# IoT_Shield.net
KiCad netlist of a schematic drawn in EAGLE
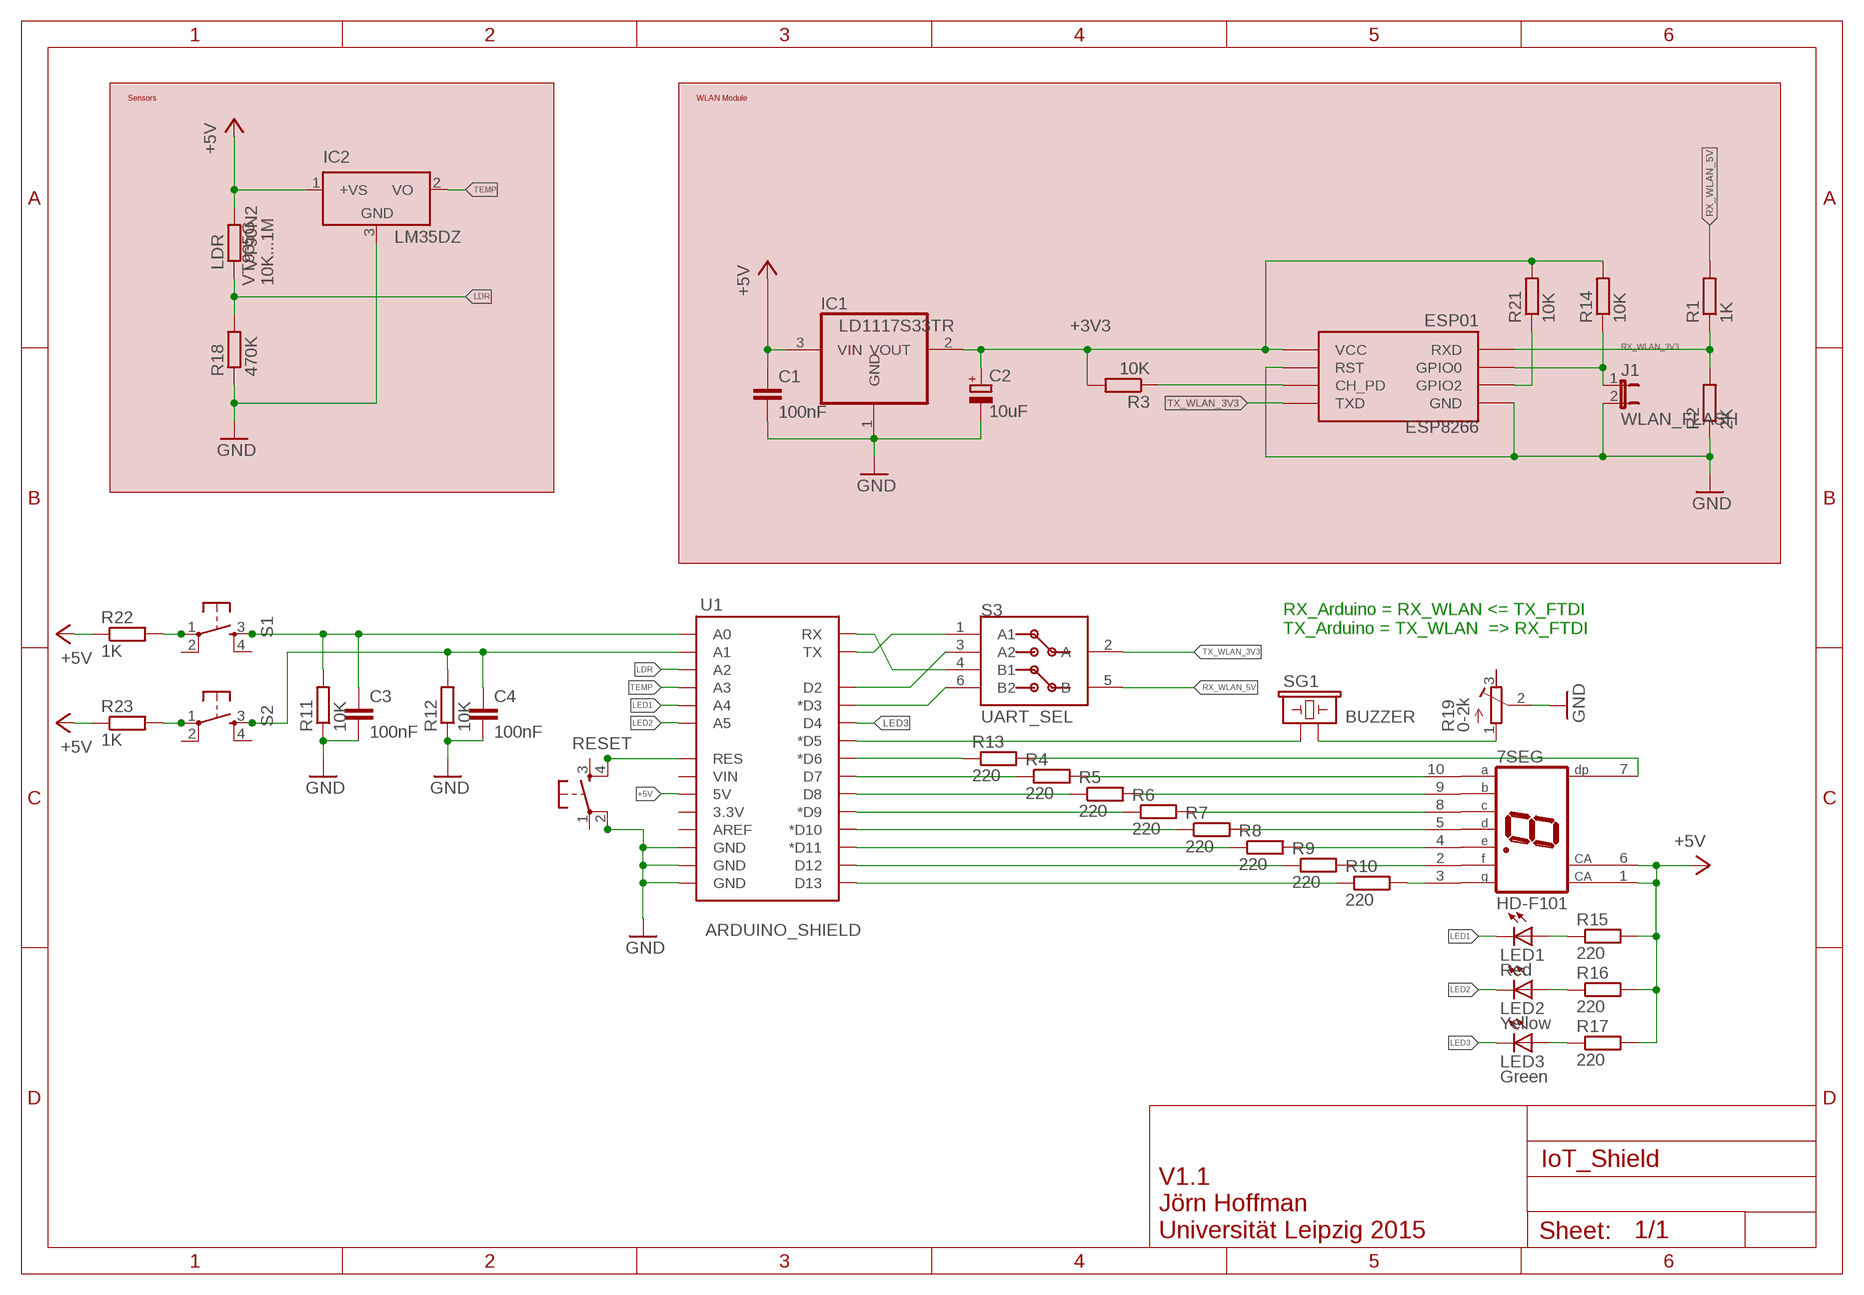
[diagram p0: schematic, sheet 1]

(export (version "E")
  (design (tool "Eeschema 10.0.6"))
  (components
    (comp (ref "7SEG")
      (value "HD-F101")
      (footprint "eagle-import:HDSP-E")
      (libsource (lib "eagle-import") (part "HD-F101"))
    )
    (comp (ref "C1")
      (value "100nF")
      (footprint "eagle-import:C0805")
      (libsource (lib "eagle-import") (part "C-EUC0805"))
    )
    (comp (ref "C2")
      (value "10uF")
      (footprint "eagle-import:A_3216-18R")
      (libsource (lib "eagle-import") (part "CPOL-EUA/3216-18R"))
    )
    (comp (ref "C3")
      (value "100nF")
      (footprint "eagle-import:C0805")
      (libsource (lib "eagle-import") (part "C-EUC0805"))
    )
    (comp (ref "C4")
      (value "100nF")
      (footprint "eagle-import:C0805")
      (libsource (lib "eagle-import") (part "C-EUC0805"))
    )
    (comp (ref "ESP8266")
      (value "ESP01")
      (footprint "eagle-import:ESP01")
      (libsource (lib "eagle-import") (part "ESP01"))
    )
    (comp (ref "IC1")
      (value "LD1117S33TR")
      (footprint "eagle-import:SOT223")
      (fields (field (name "MPN") "REG1117"))
      (libsource (lib "eagle-import") (part "REG1117"))
    )
    (comp (ref "IC2")
      (value "LM35DZ")
      (footprint "eagle-import:TO92")
      (libsource (lib "eagle-import") (part "LM35CZ"))
    )
    (comp (ref "J1")
      (value "WLAN_FLASH")
      (footprint "eagle-import:JP1")
      (libsource (lib "eagle-import") (part "JP1E"))
    )
    (comp (ref "LDR")
      (value "VT90N2")
      (footprint "eagle-import:0204V")
      (libsource (lib "eagle-import") (part "R-EU_0204/2V"))
    )
    (comp (ref "LED1")
      (value "Red")
      (footprint "eagle-import:LED5MM")
      (libsource (lib "eagle-import") (part "LED5MM"))
    )
    (comp (ref "LED2")
      (value "Yellow")
      (footprint "eagle-import:LED5MM")
      (libsource (lib "eagle-import") (part "LED5MM"))
    )
    (comp (ref "LED3")
      (value "Green")
      (footprint "eagle-import:LED5MM")
      (libsource (lib "eagle-import") (part "LED5MM"))
    )
    (comp (ref "R1")
      (value "1K")
      (footprint "eagle-import:R0805")
      (libsource (lib "eagle-import") (part "R-EU_R0805"))
    )
    (comp (ref "R2")
      (value "2K")
      (footprint "eagle-import:R0805")
      (libsource (lib "eagle-import") (part "R-EU_R0805"))
    )
    (comp (ref "R3")
      (value "10K")
      (footprint "eagle-import:R0805")
      (libsource (lib "eagle-import") (part "R-EU_R0805"))
    )
    (comp (ref "R4")
      (value "220")
      (footprint "eagle-import:R0805")
      (libsource (lib "eagle-import") (part "R-EU_R0805"))
    )
    (comp (ref "R5")
      (value "220")
      (footprint "eagle-import:R0805")
      (libsource (lib "eagle-import") (part "R-EU_R0805"))
    )
    (comp (ref "R6")
      (value "220")
      (footprint "eagle-import:R0805")
      (libsource (lib "eagle-import") (part "R-EU_R0805"))
    )
    (comp (ref "R7")
      (value "220")
      (footprint "eagle-import:R0805")
      (libsource (lib "eagle-import") (part "R-EU_R0805"))
    )
    (comp (ref "R8")
      (value "220")
      (footprint "eagle-import:R0805")
      (libsource (lib "eagle-import") (part "R-EU_R0805"))
    )
    (comp (ref "R9")
      (value "220")
      (footprint "eagle-import:R0805")
      (libsource (lib "eagle-import") (part "R-EU_R0805"))
    )
    (comp (ref "R10")
      (value "220")
      (footprint "eagle-import:R0805")
      (libsource (lib "eagle-import") (part "R-EU_R0805"))
    )
    (comp (ref "R11")
      (value "10K")
      (footprint "eagle-import:R0805")
      (libsource (lib "eagle-import") (part "R-EU_R0805"))
    )
    (comp (ref "R12")
      (value "10K")
      (footprint "eagle-import:R0805")
      (libsource (lib "eagle-import") (part "R-EU_R0805"))
    )
    (comp (ref "R13")
      (value "220")
      (footprint "eagle-import:R0805")
      (libsource (lib "eagle-import") (part "R-EU_R0805"))
    )
    (comp (ref "R14")
      (value "10K")
      (footprint "eagle-import:R0805")
      (libsource (lib "eagle-import") (part "R-EU_R0805"))
    )
    (comp (ref "R15")
      (value "220")
      (footprint "eagle-import:R0805")
      (libsource (lib "eagle-import") (part "R-EU_R0805"))
    )
    (comp (ref "R16")
      (value "220")
      (footprint "eagle-import:R0805")
      (libsource (lib "eagle-import") (part "R-EU_R0805"))
    )
    (comp (ref "R17")
      (value "220")
      (footprint "eagle-import:R0805")
      (libsource (lib "eagle-import") (part "R-EU_R0805"))
    )
    (comp (ref "R18")
      (value "470K")
      (footprint "eagle-import:R0805")
      (libsource (lib "eagle-import") (part "R-EU_R0805"))
    )
    (comp (ref "R19")
      (value "0-2k")
      (footprint "eagle-import:RTRIM4G_J")
      (libsource (lib "eagle-import") (part "R-TRIMM4G/J"))
    )
    (comp (ref "R21")
      (value "10K")
      (footprint "eagle-import:R0805")
      (libsource (lib "eagle-import") (part "R-EU_R0805"))
    )
    (comp (ref "R22")
      (value "1K")
      (footprint "eagle-import:R0805")
      (libsource (lib "eagle-import") (part "R-EU_R0805"))
    )
    (comp (ref "R23")
      (value "1K")
      (footprint "eagle-import:R0805")
      (libsource (lib "eagle-import") (part "R-EU_R0805"))
    )
    (comp (ref "RESET")
      (value "TAC_SWITCHSMD")
      (footprint "eagle-import:DTSM-6")
      (libsource (lib "eagle-import") (part "DTSM-6"))
    )
    (comp (ref "S1")
      (value "TAC_SWITCHSMD")
      (footprint "eagle-import:DTSM-6")
      (libsource (lib "eagle-import") (part "DTSM-6"))
    )
    (comp (ref "S2")
      (value "TAC_SWITCHSMD")
      (footprint "eagle-import:DTSM-6")
      (libsource (lib "eagle-import") (part "DTSM-6"))
    )
    (comp (ref "S3")
      (value "UART_SEL")
      (footprint "eagle-import:SMD")
      (libsource (lib "eagle-import") (part "JS202011SCQN"))
    )
    (comp (ref "SG1")
      (value "BUZZER")
      (footprint "eagle-import:BUZZER-12MM")
      (libsource (lib "eagle-import") (part "BUZZERPTH"))
    )
    (comp (ref "U1")
      (value "ARDUINO_SHIELD")
      (footprint "eagle-import:DUEMILANOVE_VIAS")
      (libsource (lib "eagle-import") (part "ARDUINO_SHIELDNO_SILK"))
    )
  )
  (nets
    (net (code "1") (name "+5V") (class "Default")
      (node (ref "7SEG") (pin "1") (pinfunction "CA_1") (pintype "passive"))
      (node (ref "7SEG") (pin "6") (pinfunction "CA_6") (pintype "passive"))
      (node (ref "C1") (pin "1") (pinfunction "1_1") (pintype "passive"))
      (node (ref "IC1") (pin "3") (pinfunction "VIN_3") (pintype "input"))
      (node (ref "IC2") (pin "1") (pinfunction "+VS_1") (pintype "input"))
      (node (ref "LDR") (pin "2") (pinfunction "2_2") (pintype "passive"))
      (node (ref "R15") (pin "2") (pinfunction "2_2") (pintype "passive"))
      (node (ref "R16") (pin "2") (pinfunction "2_2") (pintype "passive"))
      (node (ref "R17") (pin "2") (pinfunction "2_2") (pintype "passive"))
      (node (ref "R22") (pin "1") (pinfunction "1_1") (pintype "passive"))
      (node (ref "R23") (pin "1") (pinfunction "1_1") (pintype "passive"))
      (node (ref "U1") (pin "5V") (pinfunction "5V_5V") (pintype "bidirectional"))
    )
    (net (code "2") (name "/+3V3") (class "Default")
      (node (ref "C2") (pin "+") (pinfunction "+_+") (pintype "passive"))
      (node (ref "ESP8266") (pin "VCC") (pinfunction "VCC_VCC") (pintype "bidirectional"))
      (node (ref "IC1") (pin "2") (pinfunction "VOUT_2") (pintype "output"))
      (node (ref "R14") (pin "2") (pinfunction "2_2") (pintype "passive"))
      (node (ref "R21") (pin "2") (pinfunction "2_2") (pintype "passive"))
      (node (ref "R3") (pin "2") (pinfunction "2_2") (pintype "passive"))
    )
    (net (code "3") (name "/RX_WLAN_3V3") (class "Default")
      (node (ref "ESP8266") (pin "RX") (pinfunction "RXD_RX") (pintype "bidirectional"))
      (node (ref "R1") (pin "1") (pinfunction "1_1") (pintype "passive"))
      (node (ref "R2") (pin "2") (pinfunction "2_2") (pintype "passive"))
    )
    (net (code "4") (name "GND") (class "Default")
      (node (ref "C1") (pin "2") (pinfunction "2_2") (pintype "passive"))
      (node (ref "C2") (pin "-") (pinfunction "-_-") (pintype "passive"))
      (node (ref "C3") (pin "2") (pinfunction "2_2") (pintype "passive"))
      (node (ref "C4") (pin "2") (pinfunction "2_2") (pintype "passive"))
      (node (ref "ESP8266") (pin "GND") (pinfunction "GND_GND") (pintype "bidirectional"))
      (node (ref "ESP8266") (pin "RST") (pinfunction "RST_RST") (pintype "bidirectional"))
      (node (ref "IC1") (pin "1") (pinfunction "GND_1") (pintype "power_in"))
      (node (ref "IC2") (pin "3") (pinfunction "GND_3") (pintype "power_in"))
      (node (ref "J1") (pin "2") (pinfunction "2_2") (pintype "passive"))
      (node (ref "R11") (pin "1") (pinfunction "1_1") (pintype "passive"))
      (node (ref "R12") (pin "1") (pinfunction "1_1") (pintype "passive"))
      (node (ref "R18") (pin "1") (pinfunction "1_1") (pintype "passive"))
      (node (ref "R19") (pin "2") (pinfunction "S_2") (pintype "passive"))
      (node (ref "R2") (pin "1") (pinfunction "1_1") (pintype "passive"))
      (node (ref "RESET") (pin "2") (pinfunction "2_2") (pintype "passive"))
      (node (ref "U1") (pin "GND@0") (pinfunction "GND_GND@0") (pintype "bidirectional"))
      (node (ref "U1") (pin "GND@1") (pinfunction "GND_GND@1") (pintype "bidirectional"))
      (node (ref "U1") (pin "GND@2") (pinfunction "GND_GND@2") (pintype "bidirectional"))
    )
    (net (code "5") (name "LDR") (class "Default")
      (node (ref "LDR") (pin "1") (pinfunction "1_1") (pintype "passive"))
      (node (ref "R18") (pin "2") (pinfunction "2_2") (pintype "passive"))
      (node (ref "U1") (pin "A2") (pinfunction "A2_A2") (pintype "bidirectional"))
    )
    (net (code "6") (name "LED1") (class "Default")
      (node (ref "LED1") (pin "K") (pinfunction "C_K") (pintype "passive"))
      (node (ref "U1") (pin "A4") (pinfunction "A4_A4") (pintype "bidirectional"))
    )
    (net (code "7") (name "LED2") (class "Default")
      (node (ref "LED2") (pin "K") (pinfunction "C_K") (pintype "passive"))
      (node (ref "U1") (pin "A5") (pinfunction "A5_A5") (pintype "bidirectional"))
    )
    (net (code "8") (name "LED3") (class "Default")
      (node (ref "LED3") (pin "K") (pinfunction "C_K") (pintype "passive"))
      (node (ref "U1") (pin "D4") (pinfunction "D4_D4") (pintype "bidirectional"))
    )
    (net (code "9") (name "Net-(7SEG-A)") (class "Default")
      (node (ref "7SEG") (pin "10") (pinfunction "A_10") (pintype "passive"))
      (node (ref "R4") (pin "2") (pinfunction "2_2") (pintype "passive"))
    )
    (net (code "10") (name "Net-(7SEG-B)") (class "Default")
      (node (ref "7SEG") (pin "9") (pinfunction "B_9") (pintype "passive"))
      (node (ref "R5") (pin "2") (pinfunction "2_2") (pintype "passive"))
    )
    (net (code "11") (name "Net-(7SEG-C)") (class "Default")
      (node (ref "7SEG") (pin "8") (pinfunction "C_8") (pintype "passive"))
      (node (ref "R6") (pin "2") (pinfunction "2_2") (pintype "passive"))
    )
    (net (code "12") (name "Net-(7SEG-D)") (class "Default")
      (node (ref "7SEG") (pin "5") (pinfunction "D_5") (pintype "passive"))
      (node (ref "R7") (pin "2") (pinfunction "2_2") (pintype "passive"))
    )
    (net (code "13") (name "Net-(7SEG-DP)") (class "Default")
      (node (ref "7SEG") (pin "7") (pinfunction "DP_7") (pintype "passive"))
      (node (ref "R13") (pin "2") (pinfunction "2_2") (pintype "passive"))
    )
    (net (code "14") (name "Net-(7SEG-E)") (class "Default")
      (node (ref "7SEG") (pin "4") (pinfunction "E_4") (pintype "passive"))
      (node (ref "R8") (pin "2") (pinfunction "2_2") (pintype "passive"))
    )
    (net (code "15") (name "Net-(7SEG-F)") (class "Default")
      (node (ref "7SEG") (pin "2") (pinfunction "F_2") (pintype "passive"))
      (node (ref "R9") (pin "2") (pinfunction "2_2") (pintype "passive"))
    )
    (net (code "16") (name "Net-(7SEG-G)") (class "Default")
      (node (ref "7SEG") (pin "3") (pinfunction "G_3") (pintype "passive"))
      (node (ref "R10") (pin "2") (pinfunction "2_2") (pintype "passive"))
    )
    (net (code "17") (name "Net-(C3-Pad1)") (class "Default")
      (node (ref "C3") (pin "1") (pinfunction "1_1") (pintype "passive"))
      (node (ref "R11") (pin "2") (pinfunction "2_2") (pintype "passive"))
      (node (ref "S1") (pin "3") (pinfunction "3_3") (pintype "passive"))
      (node (ref "U1") (pin "A0") (pinfunction "A0_A0") (pintype "bidirectional"))
    )
    (net (code "18") (name "Net-(C4-Pad1)") (class "Default")
      (node (ref "C4") (pin "1") (pinfunction "1_1") (pintype "passive"))
      (node (ref "R12") (pin "2") (pinfunction "2_2") (pintype "passive"))
      (node (ref "S2") (pin "3") (pinfunction "3_3") (pintype "passive"))
      (node (ref "U1") (pin "A1") (pinfunction "A1_A1") (pintype "bidirectional"))
    )
    (net (code "19") (name "Net-(ESP8266-PadCH_PD)") (class "Default")
      (node (ref "ESP8266") (pin "CH_PD") (pinfunction "CH_PD_CH_PD") (pintype "bidirectional"))
      (node (ref "R3") (pin "1") (pinfunction "1_1") (pintype "passive"))
    )
    (net (code "20") (name "Net-(ESP8266-PadGPIO0)") (class "Default")
      (node (ref "ESP8266") (pin "GPIO0") (pinfunction "GPIO0_GPIO0") (pintype "bidirectional"))
      (node (ref "J1") (pin "1") (pinfunction "1_1") (pintype "passive"))
      (node (ref "R14") (pin "1") (pinfunction "1_1") (pintype "passive"))
    )
    (net (code "21") (name "Net-(ESP8266-PadGPIO2)") (class "Default")
      (node (ref "ESP8266") (pin "GPIO2") (pinfunction "GPIO2_GPIO2") (pintype "bidirectional"))
      (node (ref "R21") (pin "1") (pinfunction "1_1") (pintype "passive"))
    )
    (net (code "22") (name "Net-(LED1-PadA)") (class "Default")
      (node (ref "LED1") (pin "A") (pinfunction "A_A") (pintype "passive"))
      (node (ref "R15") (pin "1") (pinfunction "1_1") (pintype "passive"))
    )
    (net (code "23") (name "Net-(LED2-PadA)") (class "Default")
      (node (ref "LED2") (pin "A") (pinfunction "A_A") (pintype "passive"))
      (node (ref "R16") (pin "1") (pinfunction "1_1") (pintype "passive"))
    )
    (net (code "24") (name "Net-(LED3-PadA)") (class "Default")
      (node (ref "LED3") (pin "A") (pinfunction "A_A") (pintype "passive"))
      (node (ref "R17") (pin "1") (pinfunction "1_1") (pintype "passive"))
    )
    (net (code "25") (name "Net-(R4-Pad1)") (class "Default")
      (node (ref "R4") (pin "1") (pinfunction "1_1") (pintype "passive"))
      (node (ref "U1") (pin "D7") (pinfunction "D7_D7") (pintype "bidirectional"))
    )
    (net (code "26") (name "Net-(R5-Pad1)") (class "Default")
      (node (ref "R5") (pin "1") (pinfunction "1_1") (pintype "passive"))
      (node (ref "U1") (pin "D8") (pinfunction "D8_D8") (pintype "bidirectional"))
    )
    (net (code "27") (name "Net-(R9-Pad1)") (class "Default")
      (node (ref "R9") (pin "1") (pinfunction "1_1") (pintype "passive"))
      (node (ref "U1") (pin "D12") (pinfunction "D12_D12") (pintype "bidirectional"))
    )
    (net (code "28") (name "Net-(R10-Pad1)") (class "Default")
      (node (ref "R10") (pin "1") (pinfunction "1_1") (pintype "passive"))
      (node (ref "U1") (pin "D13") (pinfunction "D13_D13") (pintype "bidirectional"))
    )
    (net (code "29") (name "Net-(R19-A)") (class "Default")
      (node (ref "R19") (pin "1") (pinfunction "A_1") (pintype "passive"))
      (node (ref "SG1") (pin "-") (pinfunction "2_-") (pintype "passive"))
    )
    (net (code "30") (name "Net-(R22-Pad2)") (class "Default")
      (node (ref "R22") (pin "2") (pinfunction "2_2") (pintype "passive"))
      (node (ref "S1") (pin "1") (pinfunction "1_1") (pintype "passive"))
    )
    (net (code "31") (name "Net-(R23-Pad2)") (class "Default")
      (node (ref "R23") (pin "2") (pinfunction "2_2") (pintype "passive"))
      (node (ref "S2") (pin "1") (pinfunction "1_1") (pintype "passive"))
    )
    (net (code "32") (name "Net-(RESET-Pad4)") (class "Default")
      (node (ref "RESET") (pin "4") (pinfunction "4_4") (pintype "passive"))
      (node (ref "U1") (pin "RES") (pinfunction "RES_RES") (pintype "bidirectional"))
    )
    (net (code "33") (name "Net-(S3-A1)") (class "Default")
      (node (ref "S3") (pin "1") (pinfunction "A1_1") (pintype "bidirectional"))
      (node (ref "U1") (pin "TX") (pinfunction "TX_TX") (pintype "bidirectional"))
    )
    (net (code "34") (name "Net-(S3-A2)") (class "Default")
      (node (ref "S3") (pin "3") (pinfunction "A2_3") (pintype "bidirectional"))
      (node (ref "U1") (pin "D2") (pinfunction "D2_D2") (pintype "bidirectional"))
    )
    (net (code "35") (name "Net-(S3-B1)") (class "Default")
      (node (ref "S3") (pin "4") (pinfunction "B1_4") (pintype "bidirectional"))
      (node (ref "U1") (pin "RX") (pinfunction "RX_RX") (pintype "bidirectional"))
    )
    (net (code "36") (name "Net-(S3-B2)") (class "Default")
      (node (ref "S3") (pin "6") (pinfunction "B2_6") (pintype "bidirectional"))
      (node (ref "U1") (pin "D3") (pinfunction "*D3_D3") (pintype "bidirectional"))
    )
    (net (code "37") (name "Net-(SG1-1)") (class "Default")
      (node (ref "SG1") (pin "+") (pinfunction "1_+") (pintype "passive"))
      (node (ref "U1") (pin "D5") (pinfunction "*D5_D5") (pintype "bidirectional"))
    )
    (net (code "38") (name "Net-(U1-*D6)") (class "Default")
      (node (ref "R13") (pin "1") (pinfunction "1_1") (pintype "passive"))
      (node (ref "U1") (pin "D6") (pinfunction "*D6_D6") (pintype "bidirectional"))
    )
    (net (code "39") (name "Net-(U1-*D9)") (class "Default")
      (node (ref "R6") (pin "1") (pinfunction "1_1") (pintype "passive"))
      (node (ref "U1") (pin "D9") (pinfunction "*D9_D9") (pintype "bidirectional"))
    )
    (net (code "40") (name "Net-(U1-*D10)") (class "Default")
      (node (ref "R7") (pin "1") (pinfunction "1_1") (pintype "passive"))
      (node (ref "U1") (pin "D10") (pinfunction "*D10_D10") (pintype "bidirectional"))
    )
    (net (code "41") (name "Net-(U1-*D11)") (class "Default")
      (node (ref "R8") (pin "1") (pinfunction "1_1") (pintype "passive"))
      (node (ref "U1") (pin "D11") (pinfunction "*D11_D11") (pintype "bidirectional"))
    )
    (net (code "42") (name "RX_WLAN_5V") (class "Default")
      (node (ref "R1") (pin "2") (pinfunction "2_2") (pintype "passive"))
      (node (ref "S3") (pin "5") (pinfunction "B_5") (pintype "bidirectional"))
    )
    (net (code "43") (name "TEMP") (class "Default")
      (node (ref "IC2") (pin "2") (pinfunction "VO_2") (pintype "input"))
      (node (ref "U1") (pin "A3") (pinfunction "A3_A3") (pintype "bidirectional"))
    )
    (net (code "44") (name "TX_WLAN_3V3") (class "Default")
      (node (ref "ESP8266") (pin "TX") (pinfunction "TXD_TX") (pintype "bidirectional"))
      (node (ref "S3") (pin "2") (pinfunction "A_2") (pintype "bidirectional"))
    )
    (net (code "45") (name "unconnected-(R19-E-Pad3)") (class "Default")
      (node (ref "R19") (pin "3") (pinfunction "E_3") (pintype "passive"))
    )
    (net (code "46") (name "unconnected-(RESET-Pad1)") (class "Default")
      (node (ref "RESET") (pin "1") (pinfunction "1_1") (pintype "passive"))
    )
    (net (code "47") (name "unconnected-(RESET-Pad3)") (class "Default")
      (node (ref "RESET") (pin "3") (pinfunction "3_3") (pintype "passive"))
    )
    (net (code "48") (name "unconnected-(S1-Pad2)") (class "Default")
      (node (ref "S1") (pin "2") (pinfunction "2_2") (pintype "passive"))
    )
    (net (code "49") (name "unconnected-(S1-Pad4)") (class "Default")
      (node (ref "S1") (pin "4") (pinfunction "4_4") (pintype "passive"))
    )
    (net (code "50") (name "unconnected-(S2-Pad2)") (class "Default")
      (node (ref "S2") (pin "2") (pinfunction "2_2") (pintype "passive"))
    )
    (net (code "51") (name "unconnected-(S2-Pad4)") (class "Default")
      (node (ref "S2") (pin "4") (pinfunction "4_4") (pintype "passive"))
    )
    (net (code "52") (name "unconnected-(U1-Pad3.3V)") (class "Default")
      (node (ref "U1") (pin "3.3V") (pinfunction "3.3V_3.3V") (pintype "bidirectional"))
    )
    (net (code "53") (name "unconnected-(U1-PadAREF)") (class "Default")
      (node (ref "U1") (pin "AREF") (pinfunction "AREF_AREF") (pintype "bidirectional"))
    )
    (net (code "54") (name "unconnected-(U1-PadVIN)") (class "Default")
      (node (ref "U1") (pin "VIN") (pinfunction "VIN_VIN") (pintype "bidirectional"))
    )
  )
)
